# Clock.net
KiCad netlist of a schematic drawn in EAGLE
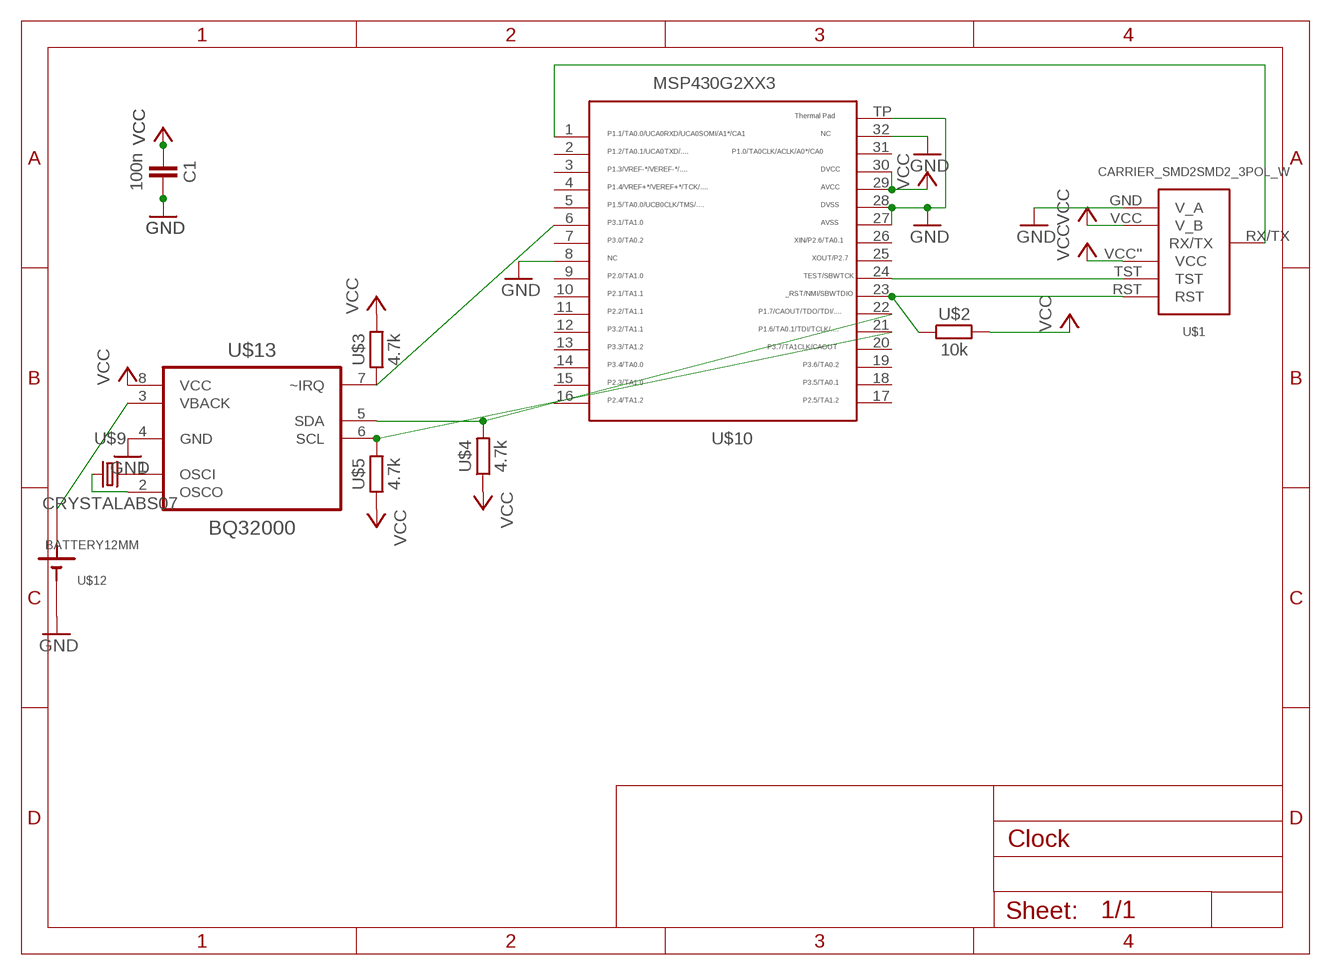
[diagram p0: schematic, sheet 1]

(export (version "E")
  (design (tool "Eeschema 10.0.6"))
  (components
    (comp (ref "C1")
      (value "100n")
      (footprint "eagle-import:603")
      (libsource (lib "eagle-import") (part "CAPACITOR"))
    )
    (comp (ref "U$1")
      (value "CARRIER_SMD2SMD2_3POL_W")
      (footprint "eagle-import:CARRIER_SMD2_WIDE_3POL")
      (libsource (lib "eagle-import") (part "CARRIER_SMD2SMD2_3POL_W"))
    )
    (comp (ref "U$2")
      (value "10k")
      (footprint "eagle-import:603")
      (libsource (lib "eagle-import") (part "RESISTOR0603"))
    )
    (comp (ref "U$3")
      (value "4.7k")
      (footprint "eagle-import:603")
      (libsource (lib "eagle-import") (part "RESISTOR0603"))
    )
    (comp (ref "U$4")
      (value "4.7k")
      (footprint "eagle-import:603")
      (libsource (lib "eagle-import") (part "RESISTOR0603"))
    )
    (comp (ref "U$5")
      (value "4.7k")
      (footprint "eagle-import:603")
      (libsource (lib "eagle-import") (part "RESISTOR0603"))
    )
    (comp (ref "U$9")
      (value "CRYSTALABS07")
      (footprint "eagle-import:ABS07")
      (libsource (lib "eagle-import") (part "CRYSTALABS07"))
    )
    (comp (ref "U$10")
      (value "MSP430G2553")
      (footprint "eagle-import:QFN32")
      (libsource (lib "eagle-import") (part "MSP430G2553"))
    )
    (comp (ref "U$12")
      (value "BATTERY12MM")
      (footprint "eagle-import:BATTERY-12MM")
      (libsource (lib "eagle-import") (part "BATTERY12MM"))
    )
    (comp (ref "U$13")
      (value "BQ32000")
      (footprint "eagle-import:SOIC8")
      (libsource (lib "eagle-import") (part "BQ32000"))
    )
  )
  (nets
    (net (code "1") (name "GND") (class "Default")
      (node (ref "C1") (pin "2") (pinfunction "2_2") (pintype "passive"))
      (node (ref "U$1") (pin "GND") (pinfunction "V_A_GND") (pintype "bidirectional"))
      (node (ref "U$10") (pin "27") (pinfunction "27_27") (pintype "bidirectional"))
      (node (ref "U$10") (pin "28") (pinfunction "28_28") (pintype "bidirectional"))
      (node (ref "U$10") (pin "32") (pinfunction "32_32") (pintype "bidirectional"))
      (node (ref "U$10") (pin "8") (pinfunction "8_8") (pintype "bidirectional"))
      (node (ref "U$10") (pin "TP") (pinfunction "TP_TP") (pintype "bidirectional"))
      (node (ref "U$12") (pin "GND") (pinfunction "-_GND") (pintype "bidirectional"))
      (node (ref "U$13") (pin "4") (pinfunction "GND_4") (pintype "passive"))
    )
    (net (code "2") (name "Net-(U$1-PadRST)") (class "Default")
      (node (ref "U$1") (pin "RST") (pinfunction "RST_RST") (pintype "bidirectional"))
      (node (ref "U$10") (pin "23") (pinfunction "23_23") (pintype "bidirectional"))
      (node (ref "U$2") (pin "1") (pinfunction "1_1") (pintype "passive"))
    )
    (net (code "3") (name "Net-(U$1-PadRX{slash}TX)") (class "Default")
      (node (ref "U$1") (pin "RX/TX") (pinfunction "RX/TX_RX/TX") (pintype "bidirectional"))
      (node (ref "U$10") (pin "1") (pinfunction "1_1") (pintype "bidirectional"))
    )
    (net (code "4") (name "Net-(U$1-PadTST)") (class "Default")
      (node (ref "U$1") (pin "TST") (pinfunction "TST_TST") (pintype "bidirectional"))
      (node (ref "U$10") (pin "24") (pinfunction "24_24") (pintype "bidirectional"))
    )
    (net (code "5") (name "Net-(U$13-OSCI)") (class "Default")
      (node (ref "U$13") (pin "1") (pinfunction "OSCI_1") (pintype "input"))
      (node (ref "U$9") (pin "2") (pinfunction "2_2") (pintype "passive"))
    )
    (net (code "6") (name "Net-(U$13-OSCO)") (class "Default")
      (node (ref "U$13") (pin "2") (pinfunction "OSCO_2") (pintype "output"))
      (node (ref "U$9") (pin "1") (pinfunction "1_1") (pintype "passive"))
    )
    (net (code "7") (name "Net-(U$13-SCL)") (class "Default")
      (node (ref "U$10") (pin "21") (pinfunction "21_21") (pintype "bidirectional"))
      (node (ref "U$13") (pin "6") (pinfunction "SCL_6") (pintype "input"))
      (node (ref "U$5") (pin "2") (pinfunction "2_2") (pintype "passive"))
    )
    (net (code "8") (name "Net-(U$13-SDA)") (class "Default")
      (node (ref "U$10") (pin "22") (pinfunction "22_22") (pintype "bidirectional"))
      (node (ref "U$13") (pin "5") (pinfunction "SDA_5") (pintype "bidirectional"))
      (node (ref "U$4") (pin "2") (pinfunction "2_2") (pintype "passive"))
    )
    (net (code "9") (name "Net-(U$13-VBACK)") (class "Default")
      (node (ref "U$12") (pin "PWR@1") (pinfunction "+_PWR@1") (pintype "bidirectional"))
      (node (ref "U$12") (pin "PWR@2") (pinfunction "+_PWR@2") (pintype "bidirectional"))
      (node (ref "U$13") (pin "3") (pinfunction "VBACK_3") (pintype "power_in"))
    )
    (net (code "10") (name "Net-(U$13-~{IRQ})") (class "Default")
      (node (ref "U$10") (pin "6") (pinfunction "6_6") (pintype "bidirectional"))
      (node (ref "U$13") (pin "7") (pinfunction "~{IRQ}_7") (pintype "output"))
      (node (ref "U$3") (pin "1") (pinfunction "1_1") (pintype "passive"))
    )
    (net (code "11") (name "VCC") (class "Default")
      (node (ref "C1") (pin "1") (pinfunction "1_1") (pintype "passive"))
      (node (ref "U$1") (pin "VCC") (pinfunction "V_B_VCC") (pintype "bidirectional"))
      (node (ref "U$1") (pin "VCC''") (pinfunction "VCC_VCC''") (pintype "bidirectional"))
      (node (ref "U$10") (pin "29") (pinfunction "29_29") (pintype "bidirectional"))
      (node (ref "U$10") (pin "30") (pinfunction "30_30") (pintype "bidirectional"))
      (node (ref "U$13") (pin "8") (pinfunction "VCC_8") (pintype "power_in"))
      (node (ref "U$2") (pin "2") (pinfunction "2_2") (pintype "passive"))
      (node (ref "U$3") (pin "2") (pinfunction "2_2") (pintype "passive"))
      (node (ref "U$4") (pin "1") (pinfunction "1_1") (pintype "passive"))
      (node (ref "U$5") (pin "1") (pinfunction "1_1") (pintype "passive"))
    )
    (net (code "12") (name "unconnected-(U$10-Pad2)") (class "Default")
      (node (ref "U$10") (pin "2") (pinfunction "2_2") (pintype "bidirectional"))
    )
    (net (code "13") (name "unconnected-(U$10-Pad3)") (class "Default")
      (node (ref "U$10") (pin "3") (pinfunction "3_3") (pintype "bidirectional"))
    )
    (net (code "14") (name "unconnected-(U$10-Pad4)") (class "Default")
      (node (ref "U$10") (pin "4") (pinfunction "4_4") (pintype "bidirectional"))
    )
    (net (code "15") (name "unconnected-(U$10-Pad5)") (class "Default")
      (node (ref "U$10") (pin "5") (pinfunction "5_5") (pintype "bidirectional"))
    )
    (net (code "16") (name "unconnected-(U$10-Pad7)") (class "Default")
      (node (ref "U$10") (pin "7") (pinfunction "7_7") (pintype "bidirectional"))
    )
    (net (code "17") (name "unconnected-(U$10-Pad9)") (class "Default")
      (node (ref "U$10") (pin "9") (pinfunction "9_9") (pintype "bidirectional"))
    )
    (net (code "18") (name "unconnected-(U$10-Pad10)") (class "Default")
      (node (ref "U$10") (pin "10") (pinfunction "10_10") (pintype "bidirectional"))
    )
    (net (code "19") (name "unconnected-(U$10-Pad11)") (class "Default")
      (node (ref "U$10") (pin "11") (pinfunction "11_11") (pintype "bidirectional"))
    )
    (net (code "20") (name "unconnected-(U$10-Pad12)") (class "Default")
      (node (ref "U$10") (pin "12") (pinfunction "12_12") (pintype "bidirectional"))
    )
    (net (code "21") (name "unconnected-(U$10-Pad13)") (class "Default")
      (node (ref "U$10") (pin "13") (pinfunction "13_13") (pintype "bidirectional"))
    )
    (net (code "22") (name "unconnected-(U$10-Pad14)") (class "Default")
      (node (ref "U$10") (pin "14") (pinfunction "14_14") (pintype "bidirectional"))
    )
    (net (code "23") (name "unconnected-(U$10-Pad15)") (class "Default")
      (node (ref "U$10") (pin "15") (pinfunction "15_15") (pintype "bidirectional"))
    )
    (net (code "24") (name "unconnected-(U$10-Pad16)") (class "Default")
      (node (ref "U$10") (pin "16") (pinfunction "16_16") (pintype "bidirectional"))
    )
    (net (code "25") (name "unconnected-(U$10-Pad17)") (class "Default")
      (node (ref "U$10") (pin "17") (pinfunction "17_17") (pintype "bidirectional"))
    )
    (net (code "26") (name "unconnected-(U$10-Pad18)") (class "Default")
      (node (ref "U$10") (pin "18") (pinfunction "18_18") (pintype "bidirectional"))
    )
    (net (code "27") (name "unconnected-(U$10-Pad19)") (class "Default")
      (node (ref "U$10") (pin "19") (pinfunction "19_19") (pintype "bidirectional"))
    )
    (net (code "28") (name "unconnected-(U$10-Pad20)") (class "Default")
      (node (ref "U$10") (pin "20") (pinfunction "20_20") (pintype "bidirectional"))
    )
    (net (code "29") (name "unconnected-(U$10-Pad25)") (class "Default")
      (node (ref "U$10") (pin "25") (pinfunction "25_25") (pintype "bidirectional"))
    )
    (net (code "30") (name "unconnected-(U$10-Pad26)") (class "Default")
      (node (ref "U$10") (pin "26") (pinfunction "26_26") (pintype "bidirectional"))
    )
    (net (code "31") (name "unconnected-(U$10-Pad31)") (class "Default")
      (node (ref "U$10") (pin "31") (pinfunction "31_31") (pintype "bidirectional"))
    )
  )
)
